# Trigger_Board.net
KiCad netlist of a schematic drawn in EAGLE
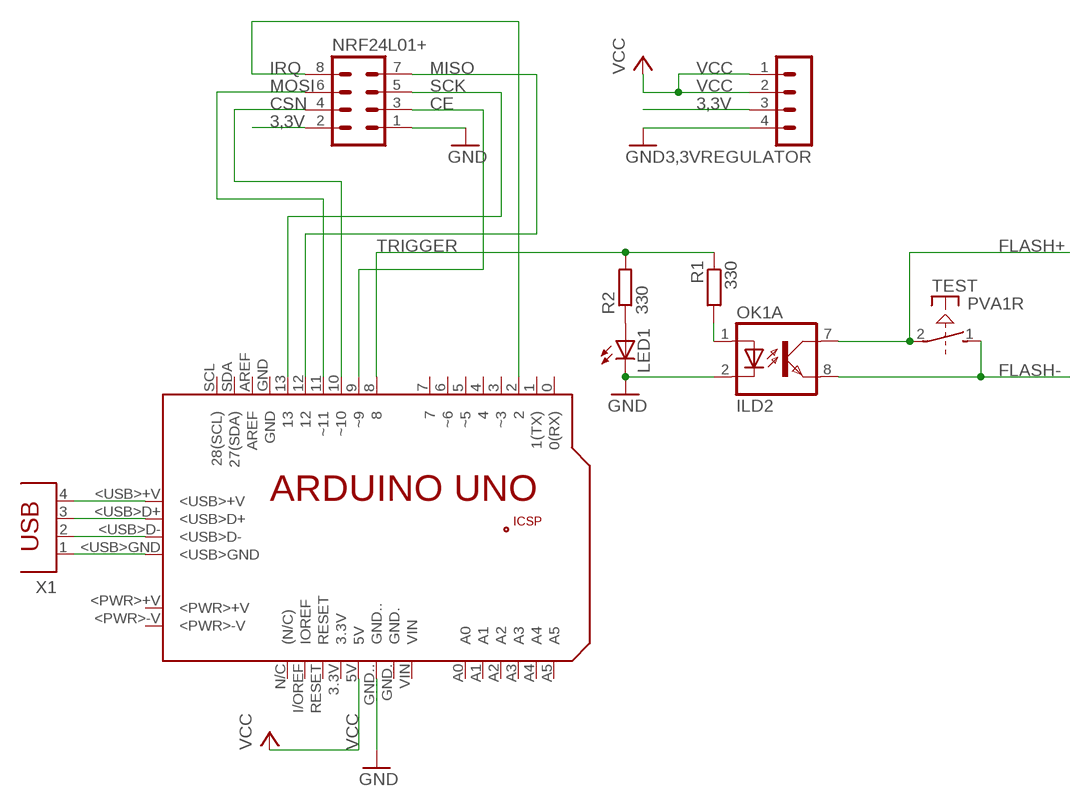
[diagram p0: schematic, sheet 1]

(export (version "E")
  (design (tool "Eeschema 10.0.6"))
  (components
    (comp (ref "3,3VREGULATOR")
      (value "MA04-1")
      (footprint "eagle-import:MA04-1")
      (libsource (lib "eagle-import") (part "MA04-1"))
    )
    (comp (ref "LED1")
      (value "LED3MM")
      (footprint "eagle-import:LED3MM")
      (libsource (lib "eagle-import") (part "LED3MM"))
    )
    (comp (ref "NRF24L01+")
      (value "MA04-2")
      (footprint "eagle-import:MA04-2")
      (libsource (lib "eagle-import") (part "MA04-2"))
    )
    (comp (ref "OK1")
      (value "ILD2")
      (footprint "eagle-import:DIL08")
      (libsource (lib "eagle-import") (part "ILD2"))
    )
    (comp (ref "PCB1")
      (value "ARDUINO_UNO")
      (footprint "eagle-import:ARDUINO_UNO")
      (libsource (lib "eagle-import") (part "ARDUINO_UNO"))
    )
    (comp (ref "R1")
      (value "330")
      (footprint "eagle-import:0207_10")
      (libsource (lib "eagle-import") (part "R-EU_0207/10"))
    )
    (comp (ref "R2")
      (value "330")
      (footprint "eagle-import:0207_10")
      (libsource (lib "eagle-import") (part "R-EU_0207/10"))
    )
    (comp (ref "TEST")
      (value "PVA1R")
      (footprint "eagle-import:PVA1R")
      (libsource (lib "eagle-import") (part "PVA1R"))
    )
    (comp (ref "X1")
      (value "PN61729")
      (footprint "eagle-import:PN61729")
      (libsource (lib "eagle-import") (part "PN61729"))
    )
  )
  (nets
    (net (code "1") (name "/3,3V") (class "Default")
      (node (ref "3,3VREGULATOR") (pin "3") (pinfunction "3_3") (pintype "passive"))
      (node (ref "NRF24L01+") (pin "2") (pinfunction "2_2") (pintype "passive"))
    )
    (net (code "2") (name "/CE") (class "Default")
      (node (ref "NRF24L01+") (pin "3") (pinfunction "3_3") (pintype "passive"))
      (node (ref "PCB1") (pin "9") (pinfunction "~{9}_9") (pintype "bidirectional"))
    )
    (net (code "3") (name "/CSN") (class "Default")
      (node (ref "NRF24L01+") (pin "4") (pinfunction "4_4") (pintype "passive"))
      (node (ref "PCB1") (pin "10") (pinfunction "~{10}_10") (pintype "bidirectional"))
    )
    (net (code "4") (name "/FLASH+") (class "Default")
      (node (ref "OK1") (pin "7") (pinfunction "COL_7") (pintype "passive"))
      (node (ref "TEST") (pin "2") (pinfunction "P_2") (pintype "passive"))
    )
    (net (code "5") (name "/FLASH-") (class "Default")
      (node (ref "OK1") (pin "8") (pinfunction "EMIT_8") (pintype "passive"))
      (node (ref "TEST") (pin "1") (pinfunction "S_1") (pintype "passive"))
    )
    (net (code "6") (name "/IRQ") (class "Default")
      (node (ref "NRF24L01+") (pin "8") (pinfunction "8_8") (pintype "passive"))
      (node (ref "PCB1") (pin "2") (pinfunction "2_2") (pintype "bidirectional"))
    )
    (net (code "7") (name "/MISO") (class "Default")
      (node (ref "NRF24L01+") (pin "7") (pinfunction "7_7") (pintype "passive"))
      (node (ref "PCB1") (pin "12") (pinfunction "12_12") (pintype "bidirectional"))
    )
    (net (code "8") (name "/MOSI") (class "Default")
      (node (ref "NRF24L01+") (pin "6") (pinfunction "6_6") (pintype "passive"))
      (node (ref "PCB1") (pin "11") (pinfunction "~{11}_11") (pintype "bidirectional"))
    )
    (net (code "9") (name "/SCK") (class "Default")
      (node (ref "NRF24L01+") (pin "5") (pinfunction "5_5") (pintype "passive"))
      (node (ref "PCB1") (pin "13") (pinfunction "13_13") (pintype "bidirectional"))
    )
    (net (code "10") (name "/TRIGGER") (class "Default")
      (node (ref "PCB1") (pin "8") (pinfunction "8_8") (pintype "bidirectional"))
      (node (ref "R1") (pin "1") (pinfunction "1_1") (pintype "passive"))
      (node (ref "R2") (pin "2") (pinfunction "2_2") (pintype "passive"))
    )
    (net (code "11") (name "GND") (class "Default")
      (node (ref "3,3VREGULATOR") (pin "4") (pinfunction "4_4") (pintype "passive"))
      (node (ref "LED1") (pin "K") (pinfunction "C_K") (pintype "passive"))
      (node (ref "NRF24L01+") (pin "1") (pinfunction "1_1") (pintype "passive"))
      (node (ref "OK1") (pin "2") (pinfunction "C_2") (pintype "passive"))
      (node (ref "PCB1") (pin "GND..") (pinfunction "GND.._GND..") (pintype "bidirectional"))
    )
    (net (code "12") (name "Net-(LED1-PadA)") (class "Default")
      (node (ref "LED1") (pin "A") (pinfunction "A_A") (pintype "passive"))
      (node (ref "R2") (pin "1") (pinfunction "1_1") (pintype "passive"))
    )
    (net (code "13") (name "Net-(OK1A-A)") (class "Default")
      (node (ref "OK1") (pin "1") (pinfunction "A_1") (pintype "passive"))
      (node (ref "R1") (pin "2") (pinfunction "2_2") (pintype "passive"))
    )
    (net (code "14") (name "Net-(PCB1-Pad<USB>+V)") (class "Default")
      (node (ref "PCB1") (pin "<USB>+V") (pinfunction "<USB>+V_<USB>+V") (pintype "bidirectional"))
      (node (ref "X1") (pin "4") (pinfunction "4_4") (pintype "passive"))
    )
    (net (code "15") (name "Net-(PCB1-Pad<USB>D+)") (class "Default")
      (node (ref "PCB1") (pin "<USB>D+") (pinfunction "<USB>D+_<USB>D+") (pintype "bidirectional"))
      (node (ref "X1") (pin "3") (pinfunction "3_3") (pintype "passive"))
    )
    (net (code "16") (name "Net-(PCB1-Pad<USB>D-)") (class "Default")
      (node (ref "PCB1") (pin "<USB>D-") (pinfunction "<USB>D-_<USB>D-") (pintype "bidirectional"))
      (node (ref "X1") (pin "2") (pinfunction "2_2") (pintype "passive"))
    )
    (net (code "17") (name "Net-(PCB1-Pad<USB>GND)") (class "Default")
      (node (ref "PCB1") (pin "<USB>GND") (pinfunction "<USB>GND_<USB>GND") (pintype "bidirectional"))
      (node (ref "X1") (pin "1") (pinfunction "1_1") (pintype "passive"))
    )
    (net (code "18") (name "VCC") (class "Default")
      (node (ref "3,3VREGULATOR") (pin "1") (pinfunction "1_1") (pintype "passive"))
      (node (ref "3,3VREGULATOR") (pin "2") (pinfunction "2_2") (pintype "passive"))
      (node (ref "PCB1") (pin "5V") (pinfunction "5V_5V") (pintype "bidirectional"))
    )
    (net (code "19") (name "unconnected-(PCB1-(N{slash}C)-PadN{slash}C)") (class "Default")
      (node (ref "PCB1") (pin "N/C") (pinfunction "(N/C)_N/C") (pintype "bidirectional"))
    )
    (net (code "20") (name "unconnected-(PCB1-0(RX)-Pad0)") (class "Default")
      (node (ref "PCB1") (pin "0") (pinfunction "0(RX)_0") (pintype "bidirectional"))
    )
    (net (code "21") (name "unconnected-(PCB1-1(TX)-Pad1)") (class "Default")
      (node (ref "PCB1") (pin "1") (pinfunction "1(TX)_1") (pintype "bidirectional"))
    )
    (net (code "22") (name "unconnected-(PCB1-27(SDA)-PadSDA)") (class "Default")
      (node (ref "PCB1") (pin "SDA") (pinfunction "27(SDA)_SDA") (pintype "bidirectional"))
    )
    (net (code "23") (name "unconnected-(PCB1-28(SCL)-PadSCL)") (class "Default")
      (node (ref "PCB1") (pin "SCL") (pinfunction "28(SCL)_SCL") (pintype "bidirectional"))
    )
    (net (code "24") (name "unconnected-(PCB1-IOREF-PadI{slash}OREF)") (class "Default")
      (node (ref "PCB1") (pin "I/OREF") (pinfunction "IOREF_I/OREF") (pintype "bidirectional"))
    )
    (net (code "25") (name "unconnected-(PCB1-Pad+5V)") (class "Default")
      (node (ref "PCB1") (pin "+5V") (pinfunction "+5V_+5V") (pintype "bidirectional"))
    )
    (net (code "26") (name "unconnected-(PCB1-Pad3.3V)") (class "Default")
      (node (ref "PCB1") (pin "3.3V") (pinfunction "3.3V_3.3V") (pintype "bidirectional"))
    )
    (net (code "27") (name "unconnected-(PCB1-Pad4)") (class "Default")
      (node (ref "PCB1") (pin "4") (pinfunction "4_4") (pintype "bidirectional"))
    )
    (net (code "28") (name "unconnected-(PCB1-Pad7)") (class "Default")
      (node (ref "PCB1") (pin "7") (pinfunction "7_7") (pintype "bidirectional"))
    )
    (net (code "29") (name "unconnected-(PCB1-Pad<PWR>+V)") (class "Default")
      (node (ref "PCB1") (pin "<PWR>+V") (pinfunction "<PWR>+V_<PWR>+V") (pintype "bidirectional"))
    )
    (net (code "30") (name "unconnected-(PCB1-Pad<PWR>-V)") (class "Default")
      (node (ref "PCB1") (pin "<PWR>-V") (pinfunction "<PWR>-V_<PWR>-V") (pintype "bidirectional"))
    )
    (net (code "31") (name "unconnected-(PCB1-PadA0)") (class "Default")
      (node (ref "PCB1") (pin "A0") (pinfunction "A0_A0") (pintype "bidirectional"))
    )
    (net (code "32") (name "unconnected-(PCB1-PadA1)") (class "Default")
      (node (ref "PCB1") (pin "A1") (pinfunction "A1_A1") (pintype "bidirectional"))
    )
    (net (code "33") (name "unconnected-(PCB1-PadA2)") (class "Default")
      (node (ref "PCB1") (pin "A2") (pinfunction "A2_A2") (pintype "bidirectional"))
    )
    (net (code "34") (name "unconnected-(PCB1-PadA3)") (class "Default")
      (node (ref "PCB1") (pin "A3") (pinfunction "A3_A3") (pintype "bidirectional"))
    )
    (net (code "35") (name "unconnected-(PCB1-PadA4)") (class "Default")
      (node (ref "PCB1") (pin "A4") (pinfunction "A4_A4") (pintype "bidirectional"))
    )
    (net (code "36") (name "unconnected-(PCB1-PadA5)") (class "Default")
      (node (ref "PCB1") (pin "A5") (pinfunction "A5_A5") (pintype "bidirectional"))
    )
    (net (code "37") (name "unconnected-(PCB1-PadAREF)") (class "Default")
      (node (ref "PCB1") (pin "AREF") (pinfunction "AREF_AREF") (pintype "bidirectional"))
    )
    (net (code "38") (name "unconnected-(PCB1-PadGND)") (class "Default")
      (node (ref "PCB1") (pin "GND") (pinfunction "GND_GND") (pintype "bidirectional"))
    )
    (net (code "39") (name "unconnected-(PCB1-PadGND.)") (class "Default")
      (node (ref "PCB1") (pin "GND.") (pinfunction "GND._GND.") (pintype "bidirectional"))
    )
    (net (code "40") (name "unconnected-(PCB1-PadGND_)") (class "Default")
      (node (ref "PCB1") (pin "GND_") (pinfunction "GND__GND_") (pintype "bidirectional"))
    )
    (net (code "41") (name "unconnected-(PCB1-PadMISO)") (class "Default")
      (node (ref "PCB1") (pin "MISO") (pinfunction "MISO_MISO") (pintype "bidirectional"))
    )
    (net (code "42") (name "unconnected-(PCB1-PadMOSI)") (class "Default")
      (node (ref "PCB1") (pin "MOSI") (pinfunction "MOSI_MOSI") (pintype "bidirectional"))
    )
    (net (code "43") (name "unconnected-(PCB1-PadRESET)") (class "Default")
      (node (ref "PCB1") (pin "RESET") (pinfunction "RESET_RESET") (pintype "bidirectional"))
    )
    (net (code "44") (name "unconnected-(PCB1-PadRESET.)") (class "Default")
      (node (ref "PCB1") (pin "RESET.") (pinfunction "RESET._RESET.") (pintype "bidirectional"))
    )
    (net (code "45") (name "unconnected-(PCB1-PadSCK)") (class "Default")
      (node (ref "PCB1") (pin "SCK") (pinfunction "SCK_SCK") (pintype "bidirectional"))
    )
    (net (code "46") (name "unconnected-(PCB1-PadVIN)") (class "Default")
      (node (ref "PCB1") (pin "VIN") (pinfunction "VIN_VIN") (pintype "bidirectional"))
    )
    (net (code "47") (name "unconnected-(PCB1-~{3}-Pad3)") (class "Default")
      (node (ref "PCB1") (pin "3") (pinfunction "~{3}_3") (pintype "bidirectional"))
    )
    (net (code "48") (name "unconnected-(PCB1-~{5}-Pad5)") (class "Default")
      (node (ref "PCB1") (pin "5") (pinfunction "~{5}_5") (pintype "bidirectional"))
    )
    (net (code "49") (name "unconnected-(PCB1-~{6}-Pad6)") (class "Default")
      (node (ref "PCB1") (pin "6") (pinfunction "~{6}_6") (pintype "bidirectional"))
    )
  )
)
